# overall_connections.net
KiCad netlist of a schematic drawn in EAGLE
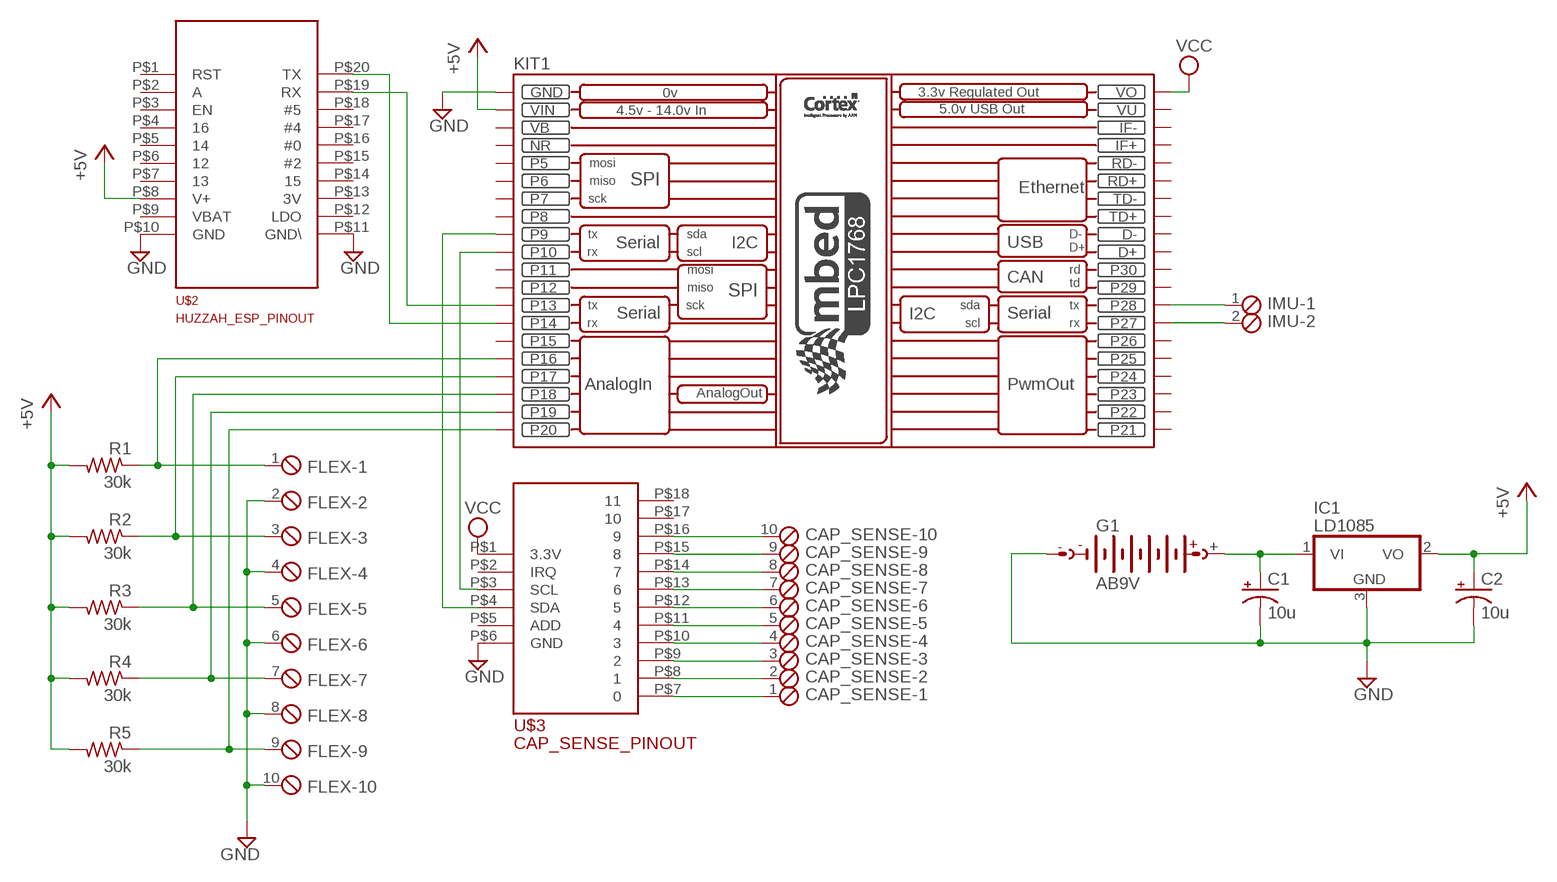
[diagram p0: schematic, sheet 1]

(export (version "E")
  (design (tool "Eeschema 10.0.6"))
  (components
    (comp (ref "C1")
      (value "10u")
      (footprint "eagle-import:E1,8-4")
      (libsource (lib "eagle-import") (part "CPOL-USE1.8-4"))
    )
    (comp (ref "C2")
      (value "10u")
      (footprint "eagle-import:E1,8-4")
      (libsource (lib "eagle-import") (part "CPOL-USE1.8-4"))
    )
    (comp (ref "CAP_SENSE")
      (value "MPT10")
      (footprint "eagle-import:10POL254")
      (libsource (lib "eagle-import") (part "MPT10"))
    )
    (comp (ref "FLEX")
      (value "MPT10")
      (footprint "eagle-import:10POL254")
      (libsource (lib "eagle-import") (part "MPT10"))
    )
    (comp (ref "G1")
      (value "AB9V")
      (footprint "eagle-import:AB9V")
      (libsource (lib "eagle-import") (part "AB9V"))
    )
    (comp (ref "IC1")
      (value "LD1085")
      (footprint "eagle-import:TO220H")
      (libsource (lib "eagle-import") (part "78T05"))
    )
    (comp (ref "IMU")
      (value "MPT2")
      (footprint "eagle-import:2POL254")
      (libsource (lib "eagle-import") (part "MPT2"))
    )
    (comp (ref "KIT1")
      (value "MBED_NXP_LPC1768")
      (footprint "eagle-import:MBED-KIT")
      (libsource (lib "eagle-import") (part "MBED_NXP_LPC1768"))
    )
    (comp (ref "R1")
      (value "30k")
      (footprint "eagle-import:0204_7")
      (libsource (lib "eagle-import") (part "R-US_0204/7"))
    )
    (comp (ref "R2")
      (value "30k")
      (footprint "eagle-import:0204_7")
      (libsource (lib "eagle-import") (part "R-US_0204/7"))
    )
    (comp (ref "R3")
      (value "30k")
      (footprint "eagle-import:0204_7")
      (libsource (lib "eagle-import") (part "R-US_0204/7"))
    )
    (comp (ref "R4")
      (value "30k")
      (footprint "eagle-import:0204_7")
      (libsource (lib "eagle-import") (part "R-US_0204/7"))
    )
    (comp (ref "R5")
      (value "30k")
      (footprint "eagle-import:0204_7")
      (libsource (lib "eagle-import") (part "R-US_0204/7"))
    )
    (comp (ref "U$2")
      (value "HUZZAH_ESP_PINOUT")
      (footprint "eagle-import:DIP20")
      (libsource (lib "eagle-import") (part "HUZZAH_ESP_PINOUT"))
    )
    (comp (ref "U$3")
      (value "CAP_SENSE_PINOUT")
      (footprint "eagle-import:DIP18")
      (libsource (lib "eagle-import") (part "CAP_SENSE_PINOUT"))
    )
  )
  (nets
    (net (code "1") (name "+5V") (class "Default")
      (node (ref "C2") (pin "+") (pinfunction "+_+") (pintype "passive"))
      (node (ref "IC1") (pin "2") (pinfunction "VO_2") (pintype "passive"))
      (node (ref "KIT1") (pin "VIN") (pinfunction "VIN_VIN") (pintype "power_in"))
      (node (ref "R1") (pin "2") (pinfunction "2_2") (pintype "passive"))
      (node (ref "R2") (pin "2") (pinfunction "2_2") (pintype "passive"))
      (node (ref "R3") (pin "2") (pinfunction "2_2") (pintype "passive"))
      (node (ref "R4") (pin "2") (pinfunction "2_2") (pintype "passive"))
      (node (ref "R5") (pin "2") (pinfunction "2_2") (pintype "passive"))
      (node (ref "U$2") (pin "P$8") (pinfunction "V+_P$8") (pintype "bidirectional"))
    )
    (net (code "2") (name "/NR") (class "Default")
      (node (ref "KIT1") (pin "NR") (pinfunction "NR_NR") (pintype "power_in"))
    )
    (net (code "3") (name "/VB") (class "Default")
      (node (ref "KIT1") (pin "VB") (pinfunction "VB_VB") (pintype "power_in"))
    )
    (net (code "4") (name "/VU") (class "Default")
      (node (ref "KIT1") (pin "VU") (pinfunction "VU_VU") (pintype "power_in"))
    )
    (net (code "5") (name "GND") (class "Default")
      (node (ref "C1") (pin "-") (pinfunction "-_-") (pintype "passive"))
      (node (ref "C2") (pin "-") (pinfunction "-_-") (pintype "passive"))
      (node (ref "FLEX") (pin "10") (pinfunction "1_10") (pintype "passive"))
      (node (ref "FLEX") (pin "2") (pinfunction "1_2") (pintype "passive"))
      (node (ref "FLEX") (pin "4") (pinfunction "1_4") (pintype "passive"))
      (node (ref "FLEX") (pin "6") (pinfunction "1_6") (pintype "passive"))
      (node (ref "FLEX") (pin "8") (pinfunction "1_8") (pintype "passive"))
      (node (ref "G1") (pin "-") (pinfunction "-_-") (pintype "passive"))
      (node (ref "IC1") (pin "3") (pinfunction "GND_3") (pintype "passive"))
      (node (ref "KIT1") (pin "GND") (pinfunction "GND_GND") (pintype "power_in"))
      (node (ref "U$2") (pin "P$10") (pinfunction "GND_P$10") (pintype "bidirectional"))
      (node (ref "U$2") (pin "P$11") (pinfunction "GND\\_P$11") (pintype "bidirectional"))
      (node (ref "U$3") (pin "P$6") (pinfunction "GND_P$6") (pintype "bidirectional"))
    )
    (net (code "6") (name "Net-(CAP_SENSEB-1)") (class "Default")
      (node (ref "CAP_SENSE") (pin "10") (pinfunction "1_10") (pintype "passive"))
      (node (ref "U$3") (pin "P$16") (pinfunction "9_P$16") (pintype "bidirectional"))
    )
    (net (code "7") (name "Net-(CAP_SENSEC-1)") (class "Default")
      (node (ref "CAP_SENSE") (pin "2") (pinfunction "1_2") (pintype "passive"))
      (node (ref "U$3") (pin "P$8") (pinfunction "1_P$8") (pintype "bidirectional"))
    )
    (net (code "8") (name "Net-(CAP_SENSED-1)") (class "Default")
      (node (ref "CAP_SENSE") (pin "3") (pinfunction "1_3") (pintype "passive"))
      (node (ref "U$3") (pin "P$9") (pinfunction "2_P$9") (pintype "bidirectional"))
    )
    (net (code "9") (name "Net-(CAP_SENSEE-1)") (class "Default")
      (node (ref "CAP_SENSE") (pin "4") (pinfunction "1_4") (pintype "passive"))
      (node (ref "U$3") (pin "P$10") (pinfunction "3_P$10") (pintype "bidirectional"))
    )
    (net (code "10") (name "Net-(CAP_SENSEF-1)") (class "Default")
      (node (ref "CAP_SENSE") (pin "5") (pinfunction "1_5") (pintype "passive"))
      (node (ref "U$3") (pin "P$11") (pinfunction "4_P$11") (pintype "bidirectional"))
    )
    (net (code "11") (name "Net-(CAP_SENSEG-1)") (class "Default")
      (node (ref "CAP_SENSE") (pin "6") (pinfunction "1_6") (pintype "passive"))
      (node (ref "U$3") (pin "P$12") (pinfunction "5_P$12") (pintype "bidirectional"))
    )
    (net (code "12") (name "Net-(CAP_SENSEH-1)") (class "Default")
      (node (ref "CAP_SENSE") (pin "7") (pinfunction "1_7") (pintype "passive"))
      (node (ref "U$3") (pin "P$13") (pinfunction "6_P$13") (pintype "bidirectional"))
    )
    (net (code "13") (name "Net-(CAP_SENSEI-1)") (class "Default")
      (node (ref "CAP_SENSE") (pin "8") (pinfunction "1_8") (pintype "passive"))
      (node (ref "U$3") (pin "P$14") (pinfunction "7_P$14") (pintype "bidirectional"))
    )
    (net (code "14") (name "Net-(CAP_SENSEJ-1)") (class "Default")
      (node (ref "CAP_SENSE") (pin "9") (pinfunction "1_9") (pintype "passive"))
      (node (ref "U$3") (pin "P$15") (pinfunction "8_P$15") (pintype "bidirectional"))
    )
    (net (code "15") (name "Net-(FLEXD-1)") (class "Default")
      (node (ref "FLEX") (pin "3") (pinfunction "1_3") (pintype "passive"))
      (node (ref "KIT1") (pin "P$17") (pinfunction "P17_P$17") (pintype "bidirectional"))
      (node (ref "R2") (pin "1") (pinfunction "1_1") (pintype "passive"))
    )
    (net (code "16") (name "Net-(FLEXF-1)") (class "Default")
      (node (ref "FLEX") (pin "5") (pinfunction "1_5") (pintype "passive"))
      (node (ref "KIT1") (pin "P$18") (pinfunction "P18_P$18") (pintype "bidirectional"))
      (node (ref "R3") (pin "1") (pinfunction "1_1") (pintype "passive"))
    )
    (net (code "17") (name "Net-(FLEXH-1)") (class "Default")
      (node (ref "FLEX") (pin "7") (pinfunction "1_7") (pintype "passive"))
      (node (ref "KIT1") (pin "P$19") (pinfunction "P19_P$19") (pintype "bidirectional"))
      (node (ref "R4") (pin "1") (pinfunction "1_1") (pintype "passive"))
    )
    (net (code "18") (name "Net-(FLEXJ-1)") (class "Default")
      (node (ref "FLEX") (pin "9") (pinfunction "1_9") (pintype "passive"))
      (node (ref "KIT1") (pin "P$20") (pinfunction "P20_P$20") (pintype "bidirectional"))
      (node (ref "R5") (pin "1") (pinfunction "1_1") (pintype "passive"))
    )
    (net (code "19") (name "Net-(IC1-VI)") (class "Default")
      (node (ref "C1") (pin "+") (pinfunction "+_+") (pintype "passive"))
      (node (ref "G1") (pin "+") (pinfunction "+_+") (pintype "passive"))
      (node (ref "IC1") (pin "1") (pinfunction "VI_1") (pintype "input"))
    )
    (net (code "20") (name "Net-(IMUB-1)") (class "Default")
      (node (ref "IMU") (pin "2") (pinfunction "1_2") (pintype "passive"))
      (node (ref "KIT1") (pin "P$27") (pinfunction "P27_P$27") (pintype "bidirectional"))
    )
    (net (code "21") (name "Net-(KIT1-P9)") (class "Default")
      (node (ref "KIT1") (pin "P$9") (pinfunction "P9_P$9") (pintype "bidirectional"))
      (node (ref "U$3") (pin "P$4") (pinfunction "SDA_P$4") (pintype "bidirectional"))
    )
    (net (code "22") (name "Net-(KIT1-P10)") (class "Default")
      (node (ref "KIT1") (pin "P$10") (pinfunction "P10_P$10") (pintype "bidirectional"))
      (node (ref "U$3") (pin "P$3") (pinfunction "SCL_P$3") (pintype "bidirectional"))
    )
    (net (code "23") (name "Net-(KIT1-P13)") (class "Default")
      (node (ref "KIT1") (pin "P$13") (pinfunction "P13_P$13") (pintype "bidirectional"))
      (node (ref "U$2") (pin "P$19") (pinfunction "RX_P$19") (pintype "bidirectional"))
    )
    (net (code "24") (name "Net-(KIT1-P14)") (class "Default")
      (node (ref "KIT1") (pin "P$14") (pinfunction "P14_P$14") (pintype "bidirectional"))
      (node (ref "U$2") (pin "P$20") (pinfunction "TX_P$20") (pintype "bidirectional"))
    )
    (net (code "25") (name "Net-(KIT1-P16)") (class "Default")
      (node (ref "FLEX") (pin "1") (pinfunction "1_1") (pintype "passive"))
      (node (ref "KIT1") (pin "P$16") (pinfunction "P16_P$16") (pintype "bidirectional"))
      (node (ref "R1") (pin "1") (pinfunction "1_1") (pintype "passive"))
    )
    (net (code "26") (name "Net-(KIT1-P28)") (class "Default")
      (node (ref "IMU") (pin "1") (pinfunction "1_1") (pintype "passive"))
      (node (ref "KIT1") (pin "P$28") (pinfunction "P28_P$28") (pintype "bidirectional"))
    )
    (net (code "27") (name "Net-(U$3-0)") (class "Default")
      (node (ref "CAP_SENSE") (pin "1") (pinfunction "1_1") (pintype "passive"))
      (node (ref "U$3") (pin "P$7") (pinfunction "0_P$7") (pintype "bidirectional"))
    )
    (net (code "28") (name "VCC") (class "Default")
      (node (ref "KIT1") (pin "VOUT") (pinfunction "VO_VOUT") (pintype "power_in"))
      (node (ref "U$3") (pin "P$1") (pinfunction "3.3V_P$1") (pintype "bidirectional"))
    )
    (net (code "29") (name "unconnected-(KIT1-P5-PadP$5)") (class "Default")
      (node (ref "KIT1") (pin "P$5") (pinfunction "P5_P$5") (pintype "bidirectional"))
    )
    (net (code "30") (name "unconnected-(KIT1-P6-PadP$6)") (class "Default")
      (node (ref "KIT1") (pin "P$6") (pinfunction "P6_P$6") (pintype "bidirectional"))
    )
    (net (code "31") (name "unconnected-(KIT1-P7-PadP$7)") (class "Default")
      (node (ref "KIT1") (pin "P$7") (pinfunction "P7_P$7") (pintype "bidirectional"))
    )
    (net (code "32") (name "unconnected-(KIT1-P8-PadP$8)") (class "Default")
      (node (ref "KIT1") (pin "P$8") (pinfunction "P8_P$8") (pintype "bidirectional"))
    )
    (net (code "33") (name "unconnected-(KIT1-P11-PadP$11)") (class "Default")
      (node (ref "KIT1") (pin "P$11") (pinfunction "P11_P$11") (pintype "bidirectional"))
    )
    (net (code "34") (name "unconnected-(KIT1-P12-PadP$12)") (class "Default")
      (node (ref "KIT1") (pin "P$12") (pinfunction "P12_P$12") (pintype "bidirectional"))
    )
    (net (code "35") (name "unconnected-(KIT1-P15-PadP$15)") (class "Default")
      (node (ref "KIT1") (pin "P$15") (pinfunction "P15_P$15") (pintype "bidirectional"))
    )
    (net (code "36") (name "unconnected-(KIT1-P21-PadP$21)") (class "Default")
      (node (ref "KIT1") (pin "P$21") (pinfunction "P21_P$21") (pintype "bidirectional"))
    )
    (net (code "37") (name "unconnected-(KIT1-P22-PadP$22)") (class "Default")
      (node (ref "KIT1") (pin "P$22") (pinfunction "P22_P$22") (pintype "bidirectional"))
    )
    (net (code "38") (name "unconnected-(KIT1-P23-PadP$23)") (class "Default")
      (node (ref "KIT1") (pin "P$23") (pinfunction "P23_P$23") (pintype "bidirectional"))
    )
    (net (code "39") (name "unconnected-(KIT1-P24-PadP$24)") (class "Default")
      (node (ref "KIT1") (pin "P$24") (pinfunction "P24_P$24") (pintype "bidirectional"))
    )
    (net (code "40") (name "unconnected-(KIT1-P25-PadP$25)") (class "Default")
      (node (ref "KIT1") (pin "P$25") (pinfunction "P25_P$25") (pintype "bidirectional"))
    )
    (net (code "41") (name "unconnected-(KIT1-P26-PadP$26)") (class "Default")
      (node (ref "KIT1") (pin "P$26") (pinfunction "P26_P$26") (pintype "bidirectional"))
    )
    (net (code "42") (name "unconnected-(KIT1-P29-PadP$29)") (class "Default")
      (node (ref "KIT1") (pin "P$29") (pinfunction "P29_P$29") (pintype "bidirectional"))
    )
    (net (code "43") (name "unconnected-(KIT1-P30-PadP$30)") (class "Default")
      (node (ref "KIT1") (pin "P$30") (pinfunction "P30_P$30") (pintype "bidirectional"))
    )
    (net (code "44") (name "unconnected-(KIT1-PadD+)") (class "Default")
      (node (ref "KIT1") (pin "D+") (pinfunction "D+_D+") (pintype "bidirectional"))
    )
    (net (code "45") (name "unconnected-(KIT1-PadD-)") (class "Default")
      (node (ref "KIT1") (pin "D-") (pinfunction "D-_D-") (pintype "bidirectional"))
    )
    (net (code "46") (name "unconnected-(KIT1-PadIF+)") (class "Default")
      (node (ref "KIT1") (pin "IF+") (pinfunction "IF+_IF+") (pintype "bidirectional"))
    )
    (net (code "47") (name "unconnected-(KIT1-PadIF-)") (class "Default")
      (node (ref "KIT1") (pin "IF-") (pinfunction "IF-_IF-") (pintype "bidirectional"))
    )
    (net (code "48") (name "unconnected-(KIT1-PadRD+)") (class "Default")
      (node (ref "KIT1") (pin "RD+") (pinfunction "RD+_RD+") (pintype "bidirectional"))
    )
    (net (code "49") (name "unconnected-(KIT1-PadRD-)") (class "Default")
      (node (ref "KIT1") (pin "RD-") (pinfunction "RD-_RD-") (pintype "bidirectional"))
    )
    (net (code "50") (name "unconnected-(KIT1-PadTD+)") (class "Default")
      (node (ref "KIT1") (pin "TD+") (pinfunction "TD+_TD+") (pintype "bidirectional"))
    )
    (net (code "51") (name "unconnected-(KIT1-PadTD-)") (class "Default")
      (node (ref "KIT1") (pin "TD-") (pinfunction "TD-_TD-") (pintype "bidirectional"))
    )
    (net (code "52") (name "unconnected-(U$2-#0-PadP$16)") (class "Default")
      (node (ref "U$2") (pin "P$16") (pinfunction "#0_P$16") (pintype "bidirectional"))
    )
    (net (code "53") (name "unconnected-(U$2-#2-PadP$15)") (class "Default")
      (node (ref "U$2") (pin "P$15") (pinfunction "#2_P$15") (pintype "bidirectional"))
    )
    (net (code "54") (name "unconnected-(U$2-#4-PadP$17)") (class "Default")
      (node (ref "U$2") (pin "P$17") (pinfunction "#4_P$17") (pintype "bidirectional"))
    )
    (net (code "55") (name "unconnected-(U$2-#5-PadP$18)") (class "Default")
      (node (ref "U$2") (pin "P$18") (pinfunction "#5_P$18") (pintype "bidirectional"))
    )
    (net (code "56") (name "unconnected-(U$2-3V-PadP$13)") (class "Default")
      (node (ref "U$2") (pin "P$13") (pinfunction "3V_P$13") (pintype "bidirectional"))
    )
    (net (code "57") (name "unconnected-(U$2-12-PadP$6)") (class "Default")
      (node (ref "U$2") (pin "P$6") (pinfunction "12_P$6") (pintype "bidirectional"))
    )
    (net (code "58") (name "unconnected-(U$2-13-PadP$7)") (class "Default")
      (node (ref "U$2") (pin "P$7") (pinfunction "13_P$7") (pintype "bidirectional"))
    )
    (net (code "59") (name "unconnected-(U$2-14-PadP$5)") (class "Default")
      (node (ref "U$2") (pin "P$5") (pinfunction "14_P$5") (pintype "bidirectional"))
    )
    (net (code "60") (name "unconnected-(U$2-15-PadP$14)") (class "Default")
      (node (ref "U$2") (pin "P$14") (pinfunction "15_P$14") (pintype "bidirectional"))
    )
    (net (code "61") (name "unconnected-(U$2-16-PadP$4)") (class "Default")
      (node (ref "U$2") (pin "P$4") (pinfunction "16_P$4") (pintype "bidirectional"))
    )
    (net (code "62") (name "unconnected-(U$2-A-PadP$2)") (class "Default")
      (node (ref "U$2") (pin "P$2") (pinfunction "A_P$2") (pintype "bidirectional"))
    )
    (net (code "63") (name "unconnected-(U$2-EN-PadP$3)") (class "Default")
      (node (ref "U$2") (pin "P$3") (pinfunction "EN_P$3") (pintype "bidirectional"))
    )
    (net (code "64") (name "unconnected-(U$2-LDO-PadP$12)") (class "Default")
      (node (ref "U$2") (pin "P$12") (pinfunction "LDO_P$12") (pintype "bidirectional"))
    )
    (net (code "65") (name "unconnected-(U$2-RST-PadP$1)") (class "Default")
      (node (ref "U$2") (pin "P$1") (pinfunction "RST_P$1") (pintype "bidirectional"))
    )
    (net (code "66") (name "unconnected-(U$2-VBAT-PadP$9)") (class "Default")
      (node (ref "U$2") (pin "P$9") (pinfunction "VBAT_P$9") (pintype "bidirectional"))
    )
    (net (code "67") (name "unconnected-(U$3-10-PadP$17)") (class "Default")
      (node (ref "U$3") (pin "P$17") (pinfunction "10_P$17") (pintype "bidirectional"))
    )
    (net (code "68") (name "unconnected-(U$3-11-PadP$18)") (class "Default")
      (node (ref "U$3") (pin "P$18") (pinfunction "11_P$18") (pintype "bidirectional"))
    )
    (net (code "69") (name "unconnected-(U$3-ADD-PadP$5)") (class "Default")
      (node (ref "U$3") (pin "P$5") (pinfunction "ADD_P$5") (pintype "bidirectional"))
    )
    (net (code "70") (name "unconnected-(U$3-IRQ-PadP$2)") (class "Default")
      (node (ref "U$3") (pin "P$2") (pinfunction "IRQ_P$2") (pintype "bidirectional"))
    )
  )
)
